# ADXL362_BOB.net
KiCad netlist of a schematic drawn in EAGLE
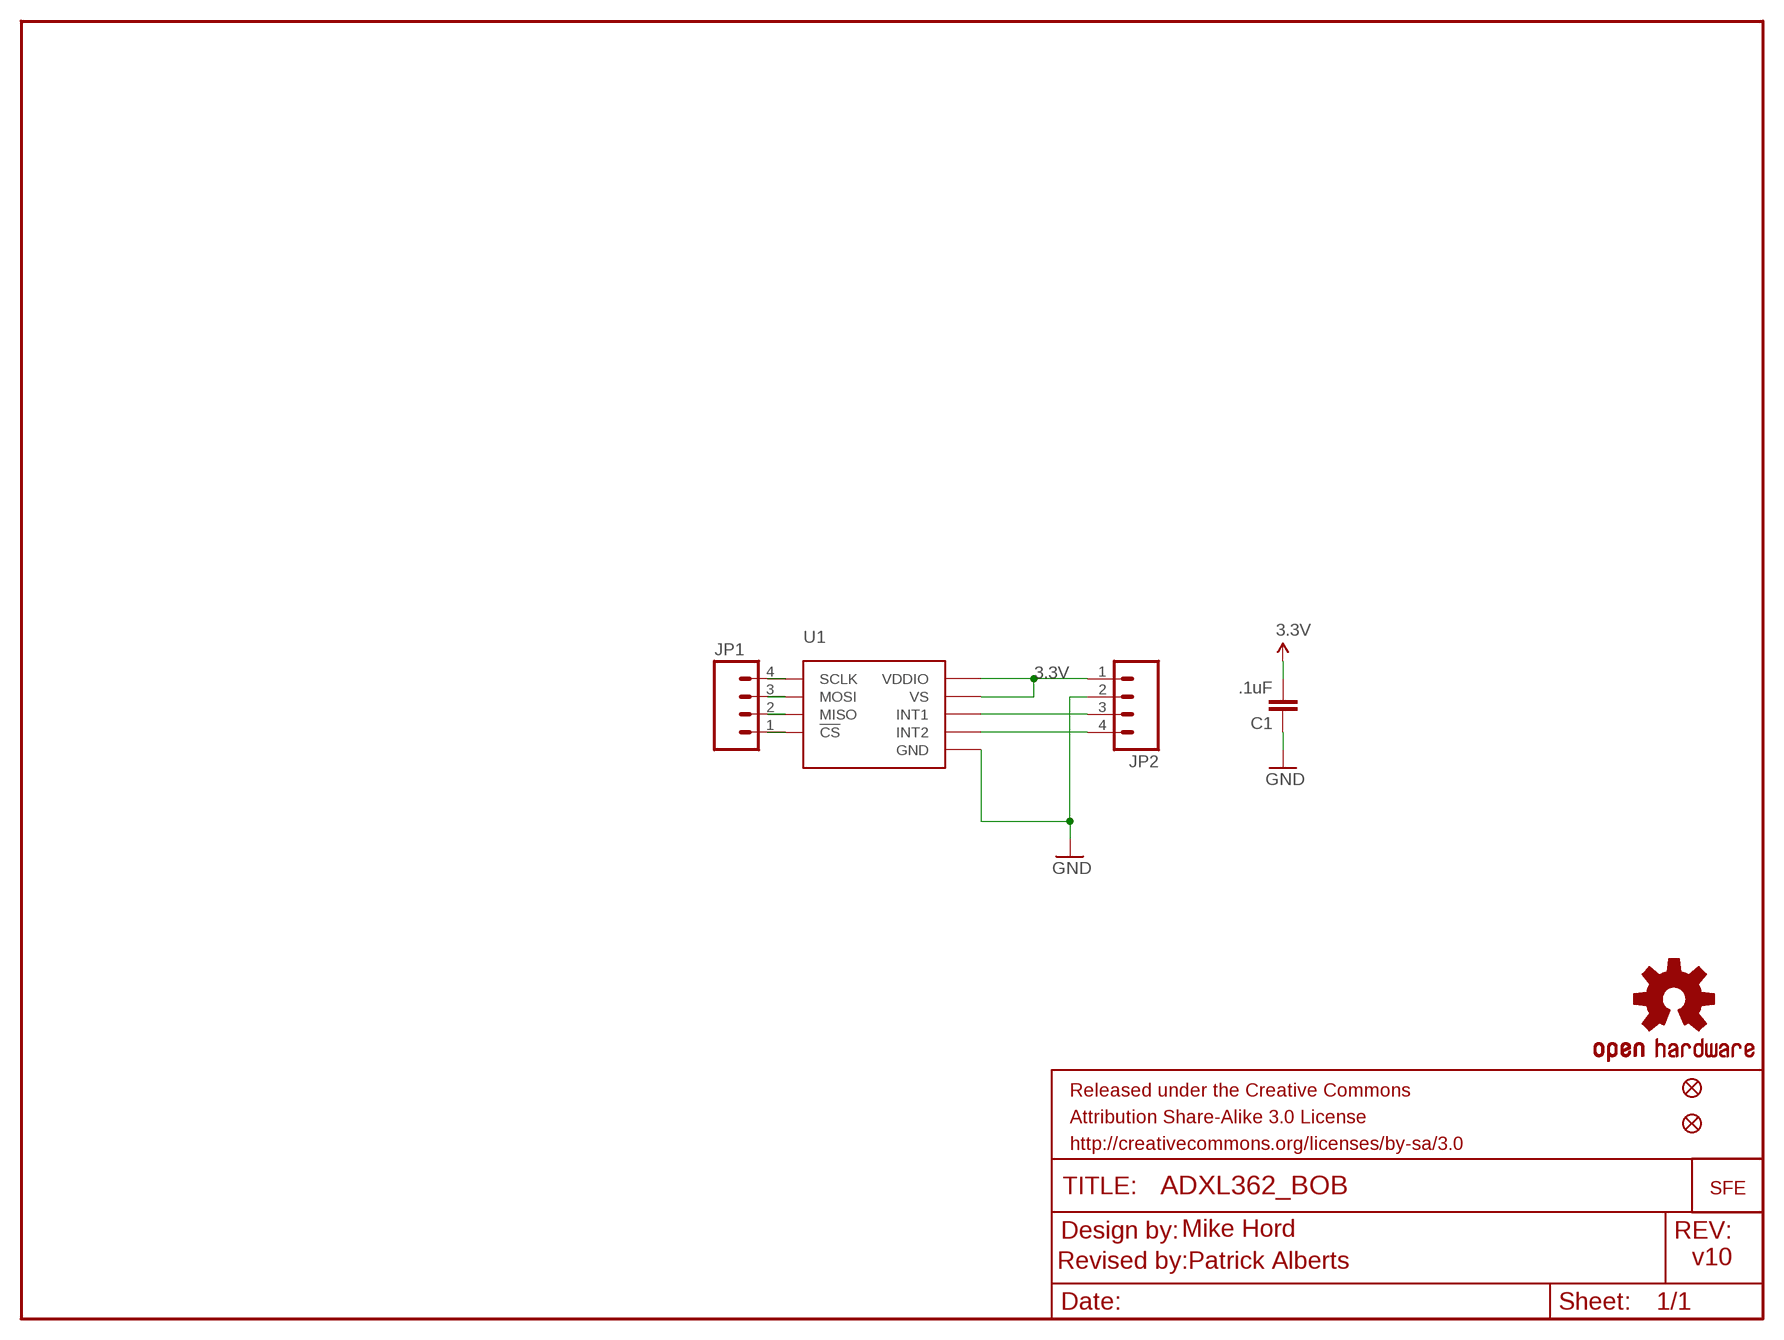
[diagram p0: schematic, sheet 1]

(export (version "E")
  (design (tool "Eeschema 10.0.6"))
  (components
    (comp (ref "C1")
      (value ".1uF")
      (footprint "eagle-import:0603-CAP")
      (fields (field (name "PROD_ID") "CAP-00810"))
      (libsource (lib "eagle-import") (part "0.1UF-25V(+80/-20%)(0603)"))
    )
    (comp (ref "FID1")
      (value "FIDUCIAL1X2")
      (footprint "eagle-import:FIDUCIAL-1X2")
      (libsource (lib "eagle-import") (part "FIDUCIAL1X2"))
    )
    (comp (ref "FID2")
      (value "FIDUCIAL1X2")
      (footprint "eagle-import:FIDUCIAL-1X2")
      (libsource (lib "eagle-import") (part "FIDUCIAL1X2"))
    )
    (comp (ref "FRAME1")
      (value "FRAME-LETTER")
      (footprint "eagle-import:CREATIVE_COMMONS")
      (libsource (lib "eagle-import") (part "FRAME-LETTER"))
    )
    (comp (ref "JP1")
      (value "M04PTH")
      (footprint "eagle-import:1X04")
      (libsource (lib "eagle-import") (part "M04PTH"))
    )
    (comp (ref "JP2")
      (value "M04PTH")
      (footprint "eagle-import:1X04")
      (libsource (lib "eagle-import") (part "M04PTH"))
    )
    (comp (ref "JP3")
      (value "LOGO-SFESK")
      (footprint "eagle-import:SFE-LOGO-FLAME")
      (libsource (lib "eagle-import") (part "LOGO-SFESK"))
    )
    (comp (ref "U$1")
      (value "OSHW-LOGOS")
      (footprint "eagle-import:OSHW-LOGO-S")
      (libsource (lib "eagle-import") (part "OSHW-LOGOS"))
    )
    (comp (ref "U1")
      (value "ADXL362ADXL362-1:1")
      (footprint "eagle-import:ADXL362-1_1")
      (libsource (lib "eagle-import") (part "ADXL362ADXL362-1{colon}1"))
    )
  )
  (nets
    (net (code "1") (name "3.3V") (class "Default")
      (node (ref "C1") (pin "2") (pinfunction "2_2") (pintype "passive"))
      (node (ref "JP2") (pin "1") (pinfunction "1_1") (pintype "passive"))
      (node (ref "U1") (pin "P$1") (pinfunction "VDDIO_P$1") (pintype "bidirectional"))
      (node (ref "U1") (pin "P$14") (pinfunction "VS_P$14") (pintype "bidirectional"))
    )
    (net (code "2") (name "GND") (class "Default")
      (node (ref "C1") (pin "1") (pinfunction "1_1") (pintype "passive"))
      (node (ref "JP2") (pin "2") (pinfunction "2_2") (pintype "passive"))
      (node (ref "U1") (pin "P$12") (pinfunction "GND_P$12") (pintype "bidirectional"))
      (node (ref "U1") (pin "P$13") (pinfunction "GND_P$13") (pintype "bidirectional"))
      (node (ref "U1") (pin "P$16") (pinfunction "GND_P$16") (pintype "bidirectional"))
    )
    (net (code "3") (name "Net-(U1-INT1)") (class "Default")
      (node (ref "JP2") (pin "3") (pinfunction "3_3") (pintype "passive"))
      (node (ref "U1") (pin "P$11") (pinfunction "INT1_P$11") (pintype "bidirectional"))
    )
    (net (code "4") (name "Net-(U1-INT2)") (class "Default")
      (node (ref "JP2") (pin "4") (pinfunction "4_4") (pintype "passive"))
      (node (ref "U1") (pin "P$9") (pinfunction "INT2_P$9") (pintype "bidirectional"))
    )
    (net (code "5") (name "Net-(U1-MISO)") (class "Default")
      (node (ref "JP1") (pin "2") (pinfunction "2_2") (pintype "passive"))
      (node (ref "U1") (pin "P$7") (pinfunction "MISO_P$7") (pintype "bidirectional"))
    )
    (net (code "6") (name "Net-(U1-MOSI)") (class "Default")
      (node (ref "JP1") (pin "3") (pinfunction "3_3") (pintype "passive"))
      (node (ref "U1") (pin "P$6") (pinfunction "MOSI_P$6") (pintype "bidirectional"))
    )
    (net (code "7") (name "Net-(U1-SCLK)") (class "Default")
      (node (ref "JP1") (pin "4") (pinfunction "4_4") (pintype "passive"))
      (node (ref "U1") (pin "P$4") (pinfunction "SCLK_P$4") (pintype "bidirectional"))
    )
    (net (code "8") (name "Net-(U1-~{CS})") (class "Default")
      (node (ref "JP1") (pin "1") (pinfunction "1_1") (pintype "passive"))
      (node (ref "U1") (pin "P$8") (pinfunction "~{CS}_P$8") (pintype "bidirectional"))
    )
  )
)
